# pcb_btt_tmc_2209.net
KiCad netlist of a schematic drawn in EAGLE
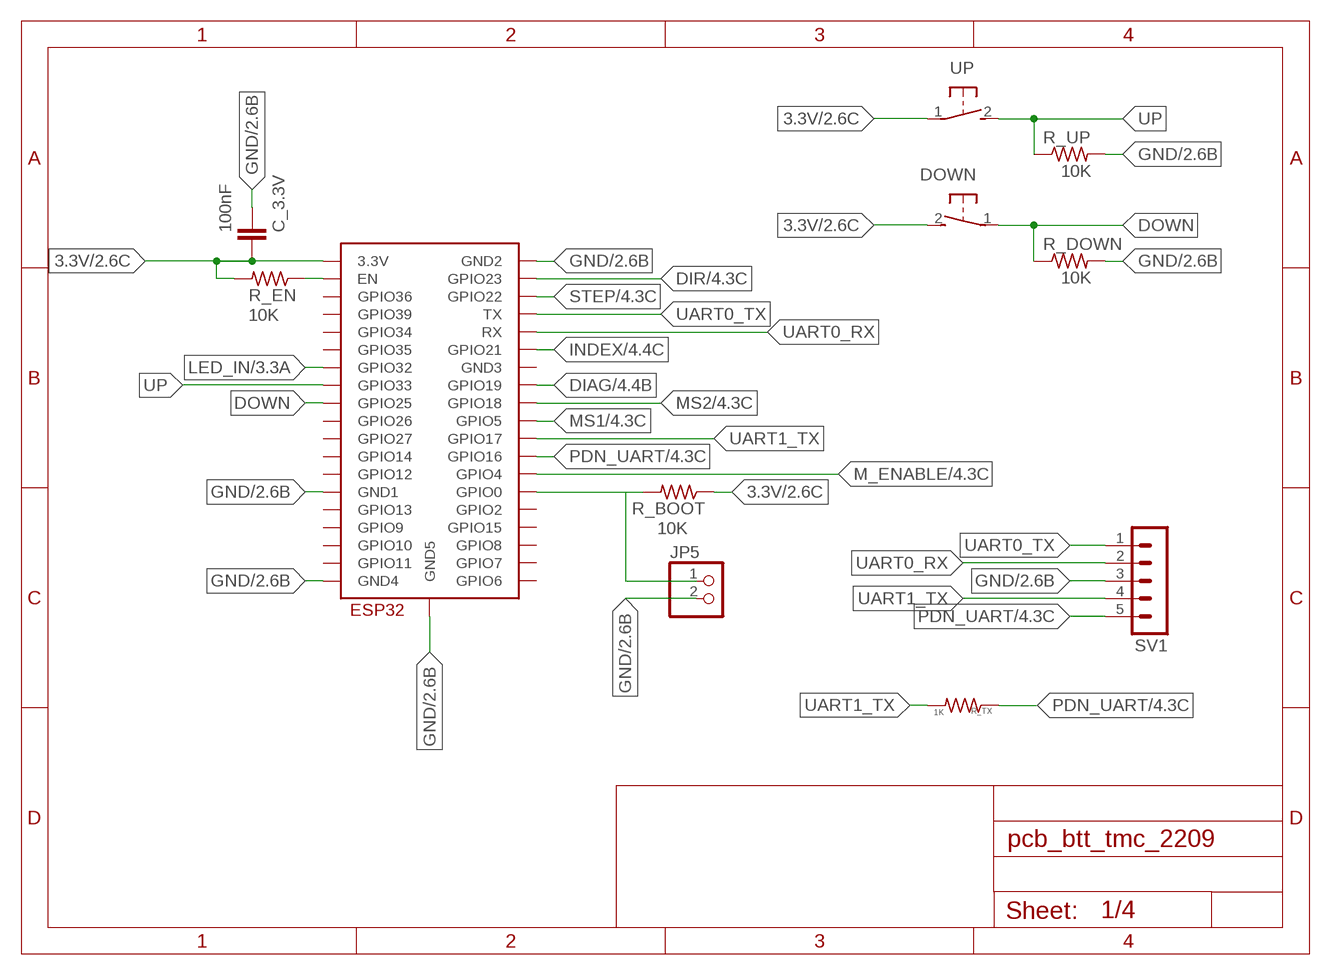
[diagram p0: schematic, sheet 1]
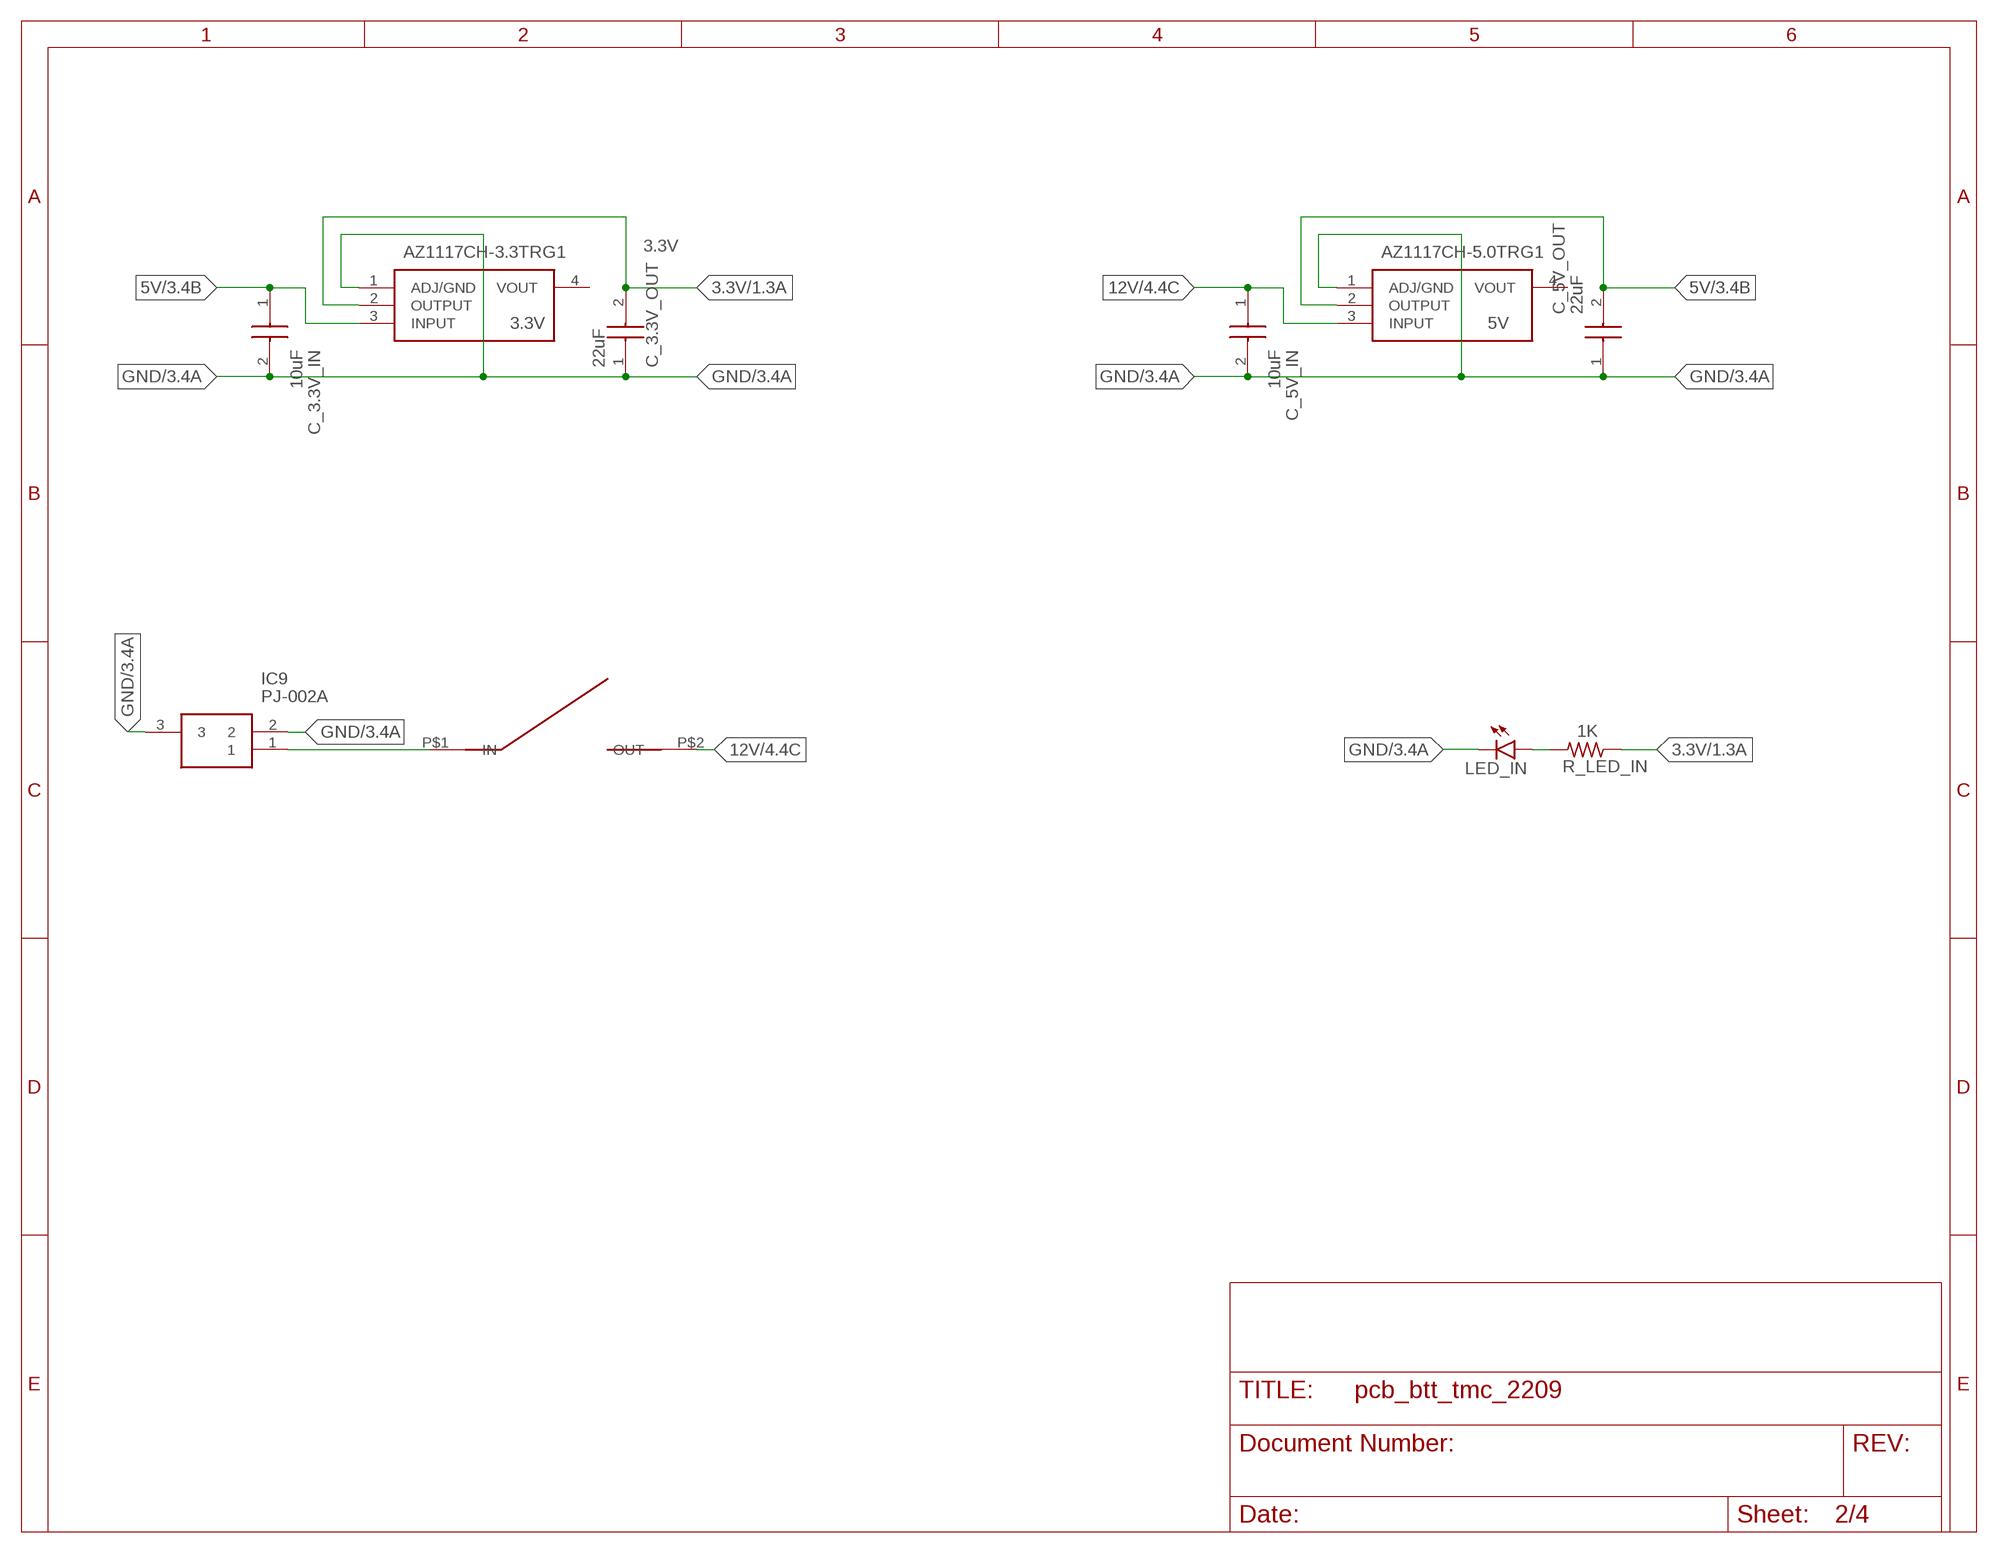
[diagram p1: schematic, sheet 2]
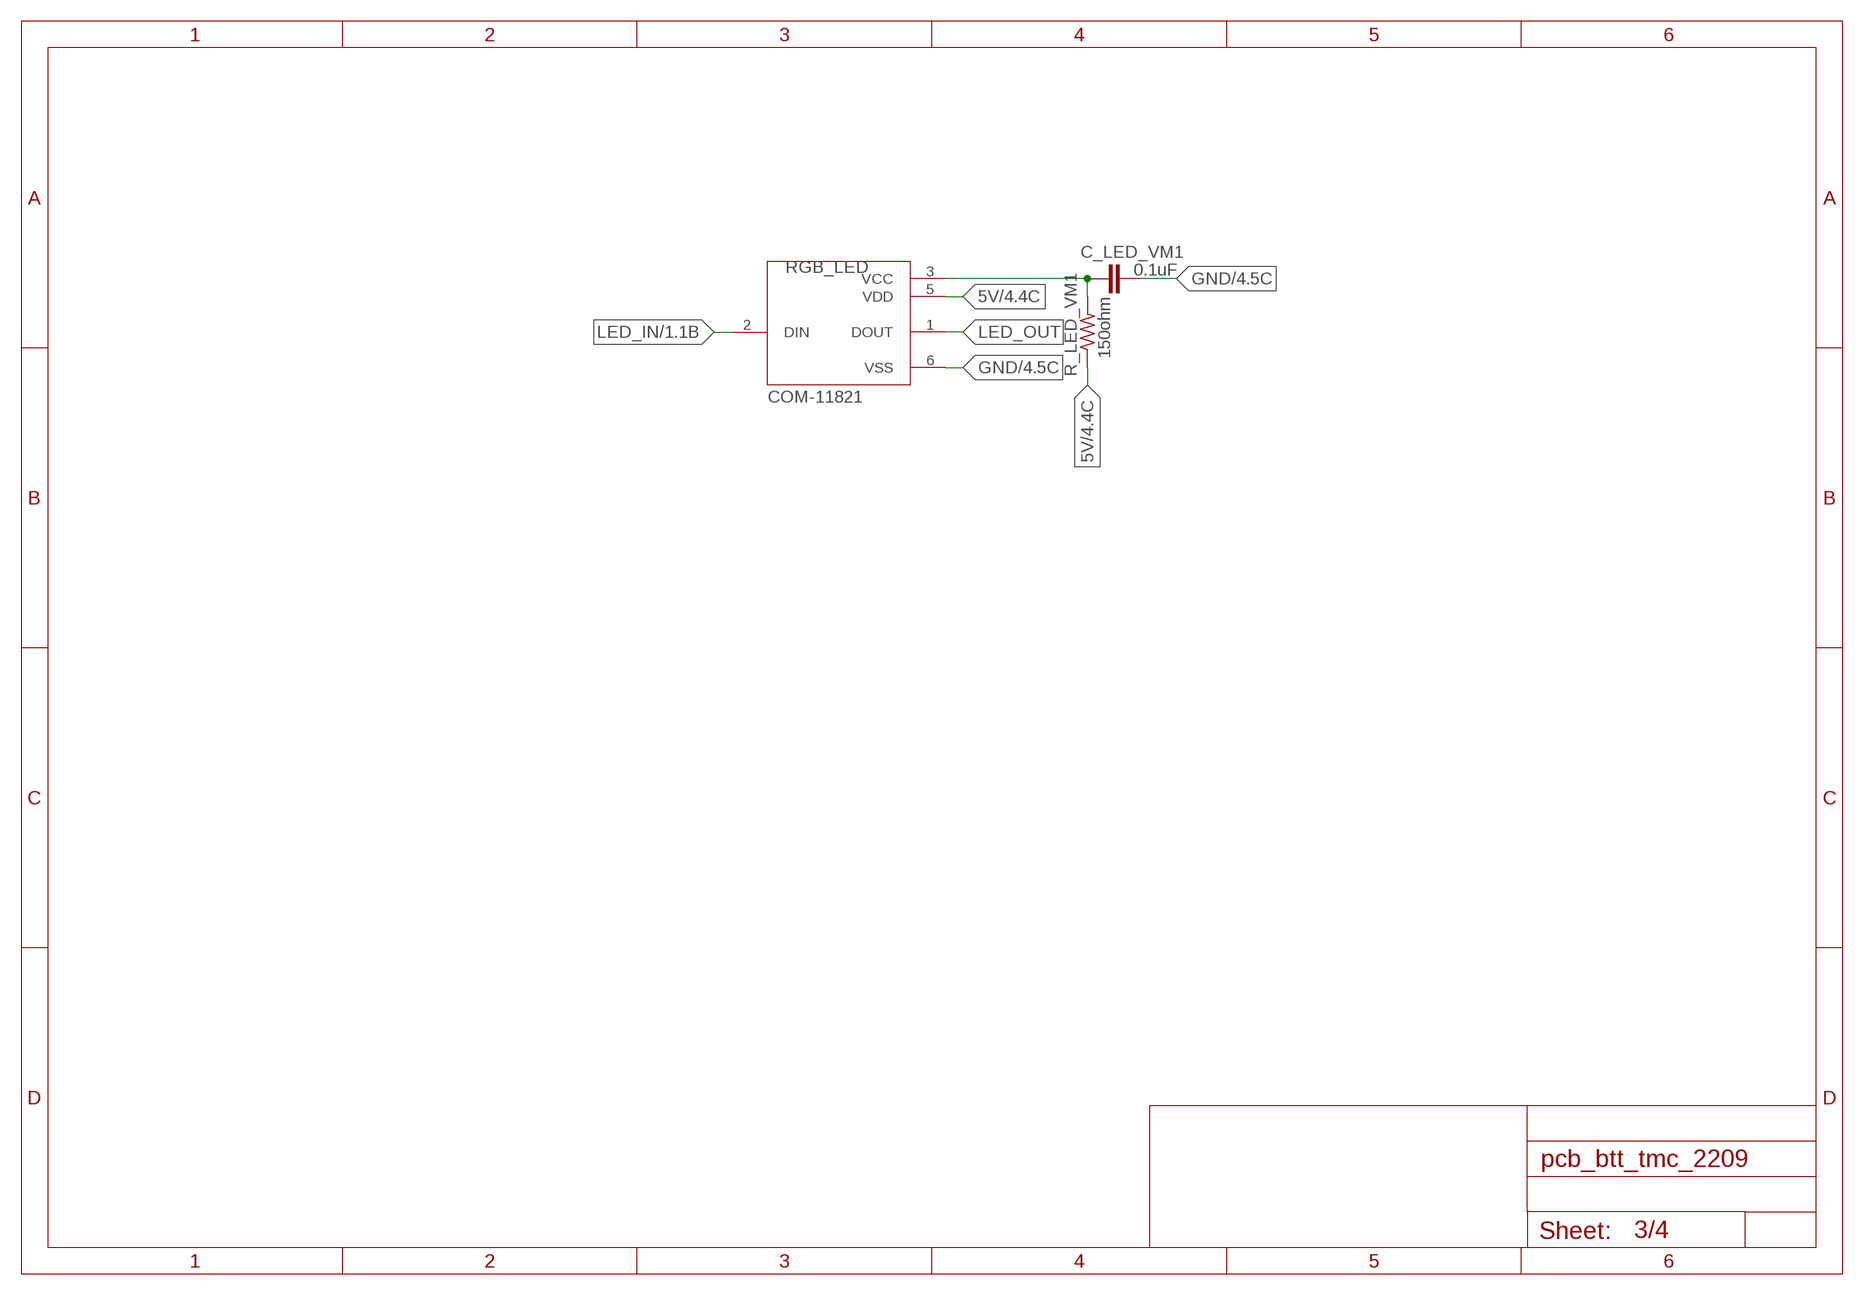
[diagram p2: schematic, sheet 3]
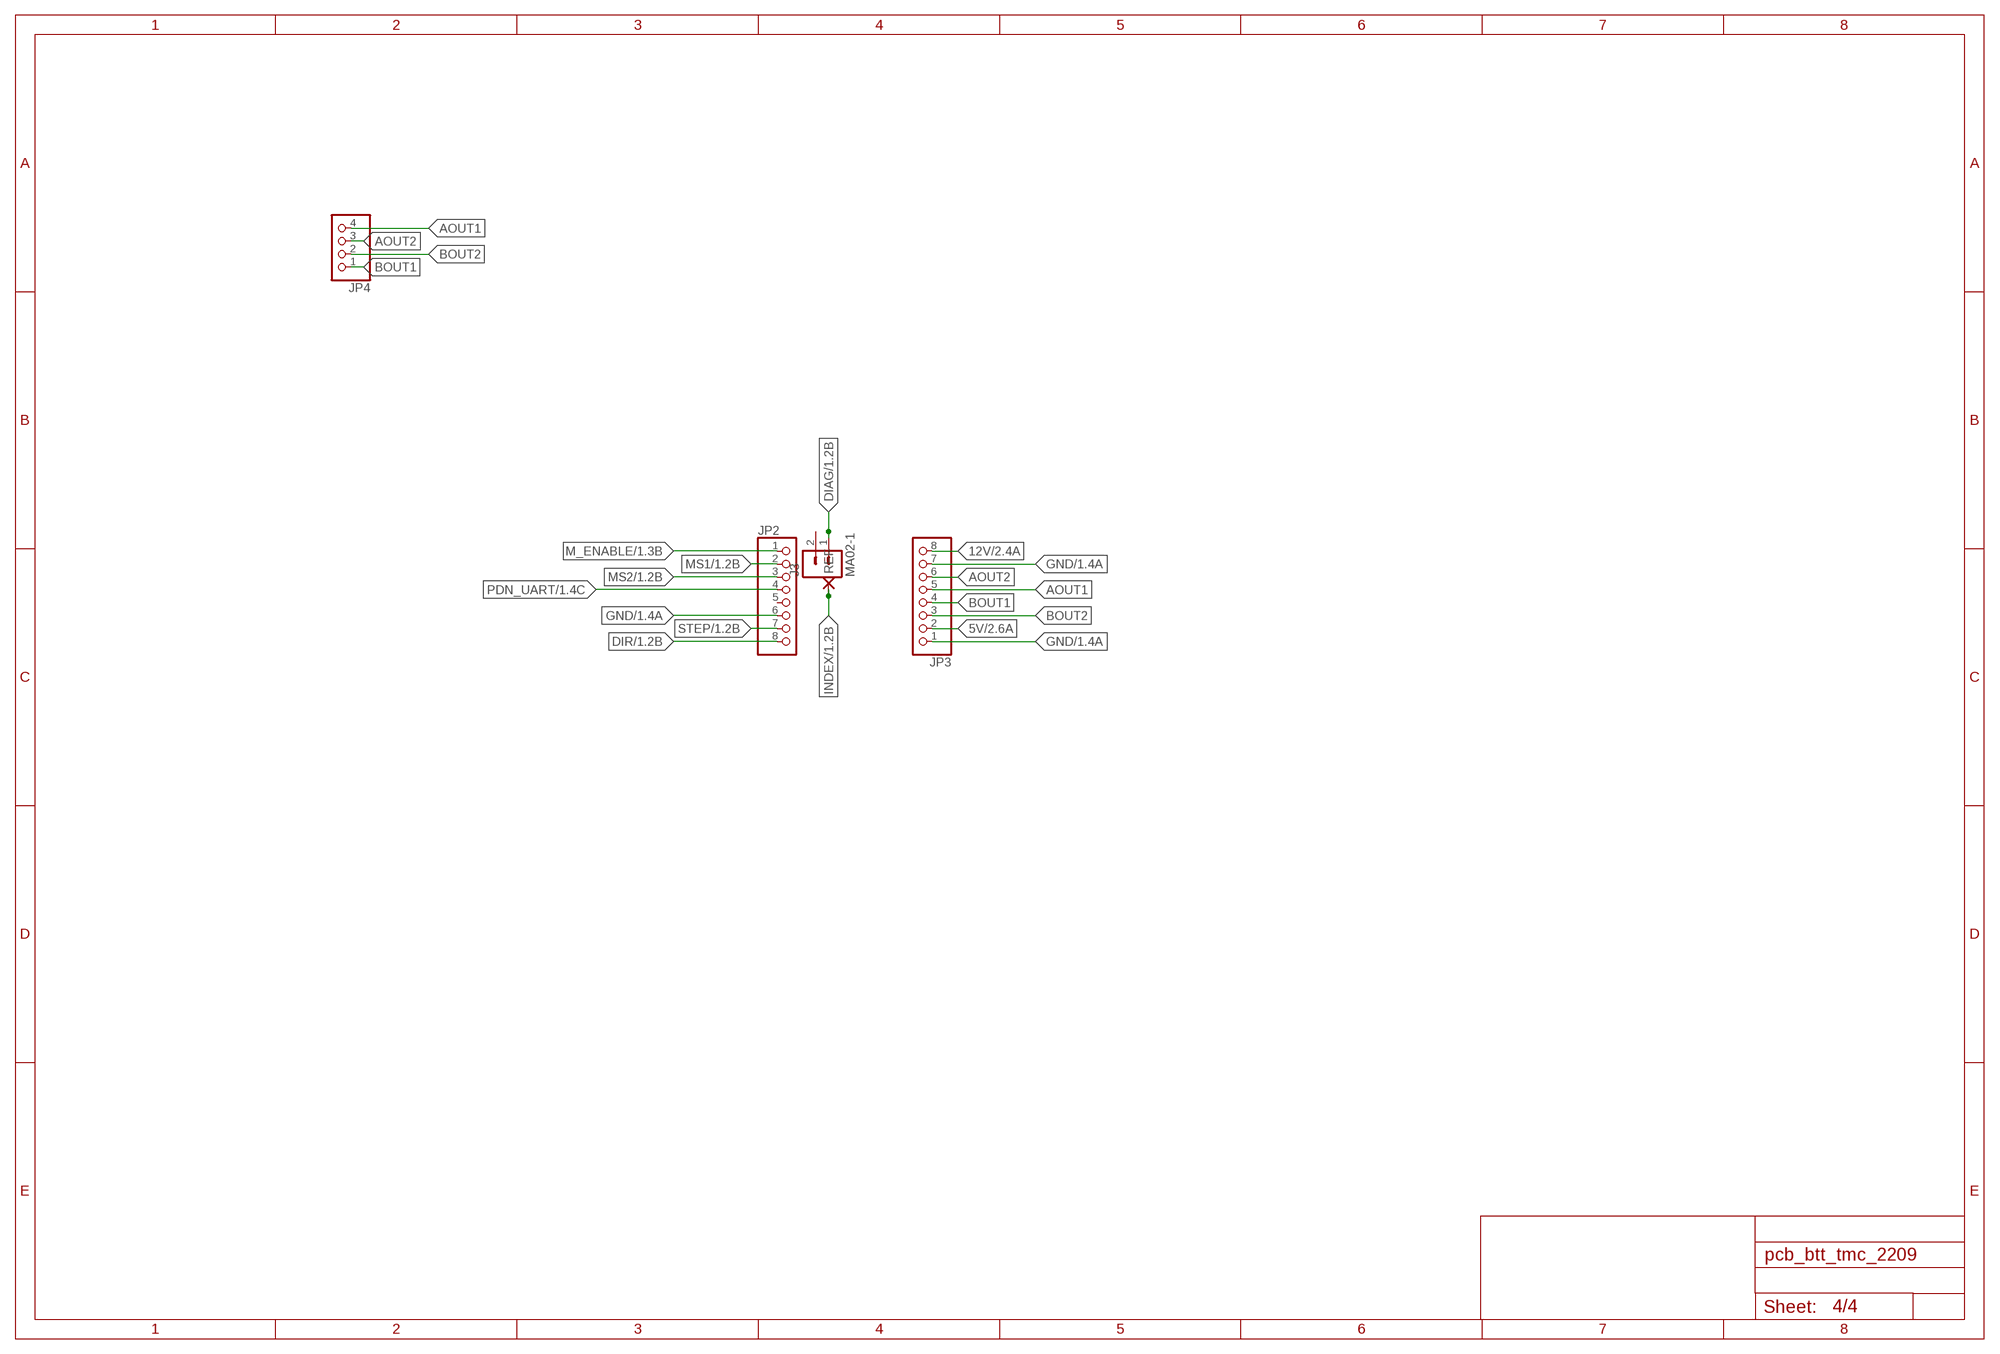
[diagram p3: schematic, sheet 4]

(export (version "E")
  (design (tool "Eeschema 10.0.6"))
  (components
    (comp (ref "C_LED_VM1")
      (value "0.1uF")
      (footprint "eagle-import:C0805K")
      (libsource (lib "eagle-import") (part "C-EUC0805K"))
    )
    (comp (ref "RGB_LED")
      (value "COM-11821")
      (footprint "eagle-import:LED_COM-11821")
      (fields (field (name "MF") "SparkFun Electronics"))
      (libsource (lib "eagle-import") (part "COM-11821"))
    )
    (comp (ref "R_LED_VM1")
      (value "150ohm")
      (footprint "eagle-import:R0805")
      (libsource (lib "eagle-import") (part "R-US_R0805"))
    )
    (comp (ref "3.3V")
      (value "AZ1117CH-3.3TRG1")
      (footprint "eagle-import:SOT230P700X180-4N")
      (fields (field (name "MOUSER_PART_NUMBER") "621-AZ1117CH-3.3TRG1"))
      (libsource (lib "eagle-import") (part "AZ1117CH-3.3TRG1"))
    )
    (comp (ref "5V")
      (value "AZ1117CH-5.0TRG1")
      (footprint "eagle-import:SOT230P700X180-4N")
      (fields (field (name "MOUSER_PART_NUMBER") "621-AZ1117CH-5.0TRG1"))
      (libsource (lib "eagle-import") (part "AZ1117CH-5.0TRG1"))
    )
    (comp (ref "C_3.3V_IN")
      (value "10uF")
      (footprint "eagle-import:CAPC2013X95N")
      (fields
        (field (name "MANUFACTURER_PART_NUMBER") "EMK212ABJ106KD-T")
        (field (name "MOUSER_PART_NUMBER") "963-EMK212ABJ106KD-T")
      )
      (libsource (lib "eagle-import") (part "EMK212ABJ106KD-T"))
    )
    (comp (ref "C_3.3V_OUT")
      (value "22uF")
      (footprint "eagle-import:CAPC3216X100N")
      (fields
        (field (name "MANUFACTURER_PART_NUMBER") "CL31A226MOCLNNC")
        (field (name "MOUSER_PART_NUMBER") "187-CL31A226MOCLNNC")
      )
      (libsource (lib "eagle-import") (part "CL31A226MOCLNNC"))
    )
    (comp (ref "C_5V_IN")
      (value "10uF")
      (footprint "eagle-import:CAPC2013X95N")
      (fields
        (field (name "MANUFACTURER_PART_NUMBER") "EMK212ABJ106KD-T")
        (field (name "MOUSER_PART_NUMBER") "963-EMK212ABJ106KD-T")
      )
      (libsource (lib "eagle-import") (part "EMK212ABJ106KD-T"))
    )
    (comp (ref "C_5V_OUT")
      (value "22uF")
      (footprint "eagle-import:CAPC3216X100N")
      (fields
        (field (name "MANUFACTURER_PART_NUMBER") "CL31A226MOCLNNC")
        (field (name "MOUSER_PART_NUMBER") "187-CL31A226MOCLNNC")
      )
      (libsource (lib "eagle-import") (part "CL31A226MOCLNNC"))
    )
    (comp (ref "IC9")
      (value "PJ-002A")
      (footprint "eagle-import:PJ002A")
      (fields (field (name "MOUSER_PART_NUMBER") "490-PJ-002A"))
      (libsource (lib "eagle-import") (part "PJ-002A"))
    )
    (comp (ref "LED_IN")
      (value "LEDSML0805")
      (footprint "eagle-import:SML0805")
      (libsource (lib "eagle-import") (part "LEDSML0805"))
    )
    (comp (ref "R_LED_IN")
      (value "1K")
      (footprint "eagle-import:R0805")
      (libsource (lib "eagle-import") (part "R-US_R0805"))
    )
    (comp (ref "U$1")
      (value "SPSTROCKERSWITCH2PIN")
      (footprint "eagle-import:SPST2PINROCKER")
      (libsource (lib "eagle-import") (part "SPSTROCKERSWITCH2PIN"))
    )
    (comp (ref "C_3.3V")
      (value "100nF")
      (footprint "eagle-import:C0805K")
      (libsource (lib "eagle-import") (part "C-EUC0805K"))
    )
    (comp (ref "DOWN")
      (value "31-XX")
      (footprint "eagle-import:B3F-31XX")
      (fields (field (name "MPN") "B3F-3100"))
      (libsource (lib "eagle-import") (part "31-XX"))
    )
    (comp (ref "JP5")
      (value "PINHD-1X2")
      (footprint "eagle-import:1X02")
      (libsource (lib "eagle-import") (part "PINHD-1X2"))
    )
    (comp (ref "R_BOOT")
      (value "10K")
      (footprint "eagle-import:R0805")
      (libsource (lib "eagle-import") (part "R-US_R0805"))
    )
    (comp (ref "R_DOWN")
      (value "10K")
      (footprint "eagle-import:R0805")
      (libsource (lib "eagle-import") (part "R-US_R0805"))
    )
    (comp (ref "R_EN")
      (value "10K")
      (footprint "eagle-import:R0805")
      (libsource (lib "eagle-import") (part "R-US_R0805"))
    )
    (comp (ref "R_TX")
      (value "1K")
      (footprint "eagle-import:R0805")
      (libsource (lib "eagle-import") (part "R-US_R0805"))
    )
    (comp (ref "R_UP")
      (value "10K")
      (footprint "eagle-import:R0805")
      (libsource (lib "eagle-import") (part "R-US_R0805"))
    )
    (comp (ref "SV1")
      (value "MA05-1")
      (footprint "eagle-import:MA05-1")
      (libsource (lib "eagle-import") (part "MA05-1"))
    )
    (comp (ref "U$2")
      (value "ESP32-WROOM")
      (footprint "eagle-import:ESP32-WROOM")
      (libsource (lib "eagle-import") (part "ESP32-WROOM"))
    )
    (comp (ref "UP")
      (value "31-XX")
      (footprint "eagle-import:B3F-31XX")
      (fields (field (name "MPN") "B3F-3100"))
      (libsource (lib "eagle-import") (part "31-XX"))
    )
    (comp (ref "J3")
      (value "MA02-1")
      (footprint "eagle-import:MA02-1")
      (libsource (lib "eagle-import") (part "MA02-1"))
    )
    (comp (ref "JP2")
      (value "PINHD-1X8")
      (footprint "eagle-import:1X08")
      (libsource (lib "eagle-import") (part "PINHD-1X8"))
    )
    (comp (ref "JP3")
      (value "PINHD-1X8")
      (footprint "eagle-import:1X08")
      (libsource (lib "eagle-import") (part "PINHD-1X8"))
    )
    (comp (ref "JP4")
      (value "PINHD-1X4")
      (footprint "eagle-import:1X04")
      (libsource (lib "eagle-import") (part "PINHD-1X4"))
    )
    (comp (ref "REF")
      (value "PAD-0.6-1.1")
      (footprint "eagle-import:PAD-0.6-1.1")
      (libsource (lib "eagle-import") (part "PAD-0.6-1.1"))
    )
  )
  (nets
    (net (code "1") (name "3.3V") (class "Default")
      (node (ref "3.3V") (pin "2") (pinfunction "OUTPUT_2") (pintype "bidirectional"))
      (node (ref "C_3.3V") (pin "2") (pinfunction "2_2") (pintype "passive"))
      (node (ref "C_3.3V_OUT") (pin "2") (pinfunction "2_2") (pintype "bidirectional"))
      (node (ref "DOWN") (pin "2") (pinfunction "S_2") (pintype "passive"))
      (node (ref "R_BOOT") (pin "1") (pinfunction "1_1") (pintype "passive"))
      (node (ref "R_EN") (pin "2") (pinfunction "2_2") (pintype "passive"))
      (node (ref "R_LED_IN") (pin "1") (pinfunction "1_1") (pintype "passive"))
      (node (ref "U$2") (pin "3V3") (pinfunction "3.3V_3V3") (pintype "bidirectional"))
      (node (ref "UP") (pin "1") (pinfunction "P_1") (pintype "passive"))
    )
    (net (code "2") (name "5V") (class "Default")
      (node (ref "3.3V") (pin "3") (pinfunction "INPUT_3") (pintype "bidirectional"))
      (node (ref "5V") (pin "2") (pinfunction "OUTPUT_2") (pintype "bidirectional"))
      (node (ref "C_3.3V_IN") (pin "1") (pinfunction "1_1") (pintype "bidirectional"))
      (node (ref "C_5V_OUT") (pin "2") (pinfunction "2_2") (pintype "bidirectional"))
      (node (ref "JP3") (pin "2") (pinfunction "2_2") (pintype "passive"))
      (node (ref "RGB_LED") (pin "5") (pinfunction "VDD_5") (pintype "power_in"))
      (node (ref "R_LED_VM1") (pin "1") (pinfunction "1_1") (pintype "passive"))
    )
    (net (code "3") (name "12V") (class "Default")
      (node (ref "5V") (pin "3") (pinfunction "INPUT_3") (pintype "bidirectional"))
      (node (ref "C_5V_IN") (pin "1") (pinfunction "1_1") (pintype "bidirectional"))
      (node (ref "JP3") (pin "8") (pinfunction "8_8") (pintype "passive"))
      (node (ref "U$1") (pin "P$2") (pinfunction "OUT_P$2") (pintype "bidirectional"))
    )
    (net (code "4") (name "AOUT1") (class "Default")
      (node (ref "JP3") (pin "5") (pinfunction "5_5") (pintype "passive"))
      (node (ref "JP4") (pin "4") (pinfunction "4_4") (pintype "passive"))
    )
    (net (code "5") (name "AOUT2") (class "Default")
      (node (ref "JP3") (pin "6") (pinfunction "6_6") (pintype "passive"))
      (node (ref "JP4") (pin "3") (pinfunction "3_3") (pintype "passive"))
    )
    (net (code "6") (name "BOUT1") (class "Default")
      (node (ref "JP3") (pin "4") (pinfunction "4_4") (pintype "passive"))
      (node (ref "JP4") (pin "1") (pinfunction "1_1") (pintype "passive"))
    )
    (net (code "7") (name "BOUT2") (class "Default")
      (node (ref "JP3") (pin "3") (pinfunction "3_3") (pintype "passive"))
      (node (ref "JP4") (pin "2") (pinfunction "2_2") (pintype "passive"))
    )
    (net (code "8") (name "DIAG") (class "Default")
      (node (ref "J3") (pin "1") (pinfunction "1_1") (pintype "passive"))
      (node (ref "U$2") (pin "IO19") (pinfunction "GPIO19_IO19") (pintype "bidirectional"))
    )
    (net (code "9") (name "DIR") (class "Default")
      (node (ref "JP2") (pin "8") (pinfunction "8_8") (pintype "passive"))
      (node (ref "U$2") (pin "IO23") (pinfunction "GPIO23_IO23") (pintype "bidirectional"))
    )
    (net (code "10") (name "DOWN") (class "Default")
      (node (ref "DOWN") (pin "1") (pinfunction "P_1") (pintype "passive"))
      (node (ref "R_DOWN") (pin "1") (pinfunction "1_1") (pintype "passive"))
      (node (ref "U$2") (pin "IO25") (pinfunction "GPIO25_IO25") (pintype "bidirectional"))
    )
    (net (code "11") (name "GND") (class "Default")
      (node (ref "3.3V") (pin "1") (pinfunction "ADJ/GND_1") (pintype "bidirectional"))
      (node (ref "5V") (pin "1") (pinfunction "ADJ/GND_1") (pintype "bidirectional"))
      (node (ref "C_3.3V") (pin "1") (pinfunction "1_1") (pintype "passive"))
      (node (ref "C_3.3V_IN") (pin "2") (pinfunction "2_2") (pintype "bidirectional"))
      (node (ref "C_3.3V_OUT") (pin "1") (pinfunction "1_1") (pintype "bidirectional"))
      (node (ref "C_5V_IN") (pin "2") (pinfunction "2_2") (pintype "bidirectional"))
      (node (ref "C_5V_OUT") (pin "1") (pinfunction "1_1") (pintype "bidirectional"))
      (node (ref "C_LED_VM1") (pin "2") (pinfunction "2_2") (pintype "passive"))
      (node (ref "IC9") (pin "2") (pinfunction "2_2") (pintype "bidirectional"))
      (node (ref "IC9") (pin "3") (pinfunction "3_3") (pintype "bidirectional"))
      (node (ref "JP2") (pin "6") (pinfunction "6_6") (pintype "passive"))
      (node (ref "JP3") (pin "1") (pinfunction "1_1") (pintype "passive"))
      (node (ref "JP3") (pin "7") (pinfunction "7_7") (pintype "passive"))
      (node (ref "JP5") (pin "2") (pinfunction "2_2") (pintype "passive"))
      (node (ref "LED_IN") (pin "C") (pinfunction "C_C") (pintype "passive"))
      (node (ref "RGB_LED") (pin "6") (pinfunction "VSS_6") (pintype "power_in"))
      (node (ref "R_DOWN") (pin "2") (pinfunction "2_2") (pintype "passive"))
      (node (ref "R_UP") (pin "2") (pinfunction "2_2") (pintype "passive"))
      (node (ref "SV1") (pin "3") (pinfunction "3_3") (pintype "passive"))
      (node (ref "U$2") (pin "GND1") (pinfunction "GND1_GND1") (pintype "bidirectional"))
      (node (ref "U$2") (pin "GND2") (pinfunction "GND2_GND2") (pintype "bidirectional"))
      (node (ref "U$2") (pin "GND4") (pinfunction "GND4_GND4") (pintype "bidirectional"))
      (node (ref "U$2") (pin "GND5") (pinfunction "GND5_GND5") (pintype "bidirectional"))
    )
    (net (code "12") (name "INDEX") (class "Default")
      (node (ref "REF") (pin "1") (pinfunction "P_1") (pintype "passive"))
      (node (ref "U$2") (pin "IO21") (pinfunction "GPIO21_IO21") (pintype "bidirectional"))
    )
    (net (code "13") (name "LED_IN") (class "Default")
      (node (ref "RGB_LED") (pin "2") (pinfunction "DIN_2") (pintype "input"))
      (node (ref "U$2") (pin "IO32") (pinfunction "GPIO32_IO32") (pintype "bidirectional"))
    )
    (net (code "14") (name "LED_OUT") (class "Default")
      (node (ref "RGB_LED") (pin "1") (pinfunction "DOUT_1") (pintype "output"))
    )
    (net (code "15") (name "MS1") (class "Default")
      (node (ref "JP2") (pin "2") (pinfunction "2_2") (pintype "passive"))
      (node (ref "U$2") (pin "IO5") (pinfunction "GPIO5_IO5") (pintype "bidirectional"))
    )
    (net (code "16") (name "MS2") (class "Default")
      (node (ref "JP2") (pin "3") (pinfunction "3_3") (pintype "passive"))
      (node (ref "U$2") (pin "IO18") (pinfunction "GPIO18_IO18") (pintype "bidirectional"))
    )
    (net (code "17") (name "M_ENABLE") (class "Default")
      (node (ref "JP2") (pin "1") (pinfunction "1_1") (pintype "passive"))
      (node (ref "U$2") (pin "IO4") (pinfunction "GPIO4_IO4") (pintype "bidirectional"))
    )
    (net (code "18") (name "Net-(LED_IN-PadA)") (class "Default")
      (node (ref "LED_IN") (pin "A") (pinfunction "A_A") (pintype "passive"))
      (node (ref "R_LED_IN") (pin "2") (pinfunction "2_2") (pintype "passive"))
    )
    (net (code "19") (name "Net-(RGB_LED-VCC)") (class "Default")
      (node (ref "C_LED_VM1") (pin "1") (pinfunction "1_1") (pintype "passive"))
      (node (ref "RGB_LED") (pin "3") (pinfunction "VCC_3") (pintype "power_in"))
      (node (ref "R_LED_VM1") (pin "2") (pinfunction "2_2") (pintype "passive"))
    )
    (net (code "20") (name "Net-(R_EN-Pad1)") (class "Default")
      (node (ref "R_EN") (pin "1") (pinfunction "1_1") (pintype "passive"))
      (node (ref "U$2") (pin "EN") (pinfunction "EN_EN") (pintype "bidirectional"))
    )
    (net (code "21") (name "Net-(U$1-IN)") (class "Default")
      (node (ref "IC9") (pin "1") (pinfunction "1_1") (pintype "bidirectional"))
      (node (ref "U$1") (pin "P$1") (pinfunction "IN_P$1") (pintype "bidirectional"))
    )
    (net (code "22") (name "Net-(U$2-GPIO0)") (class "Default")
      (node (ref "JP5") (pin "1") (pinfunction "1_1") (pintype "passive"))
      (node (ref "R_BOOT") (pin "2") (pinfunction "2_2") (pintype "passive"))
      (node (ref "U$2") (pin "IO0") (pinfunction "GPIO0_IO0") (pintype "bidirectional"))
    )
    (net (code "23") (name "PDN_UART") (class "Default")
      (node (ref "JP2") (pin "4") (pinfunction "4_4") (pintype "passive"))
      (node (ref "R_TX") (pin "1") (pinfunction "1_1") (pintype "passive"))
      (node (ref "SV1") (pin "5") (pinfunction "5_5") (pintype "passive"))
      (node (ref "U$2") (pin "IO16") (pinfunction "GPIO16_IO16") (pintype "bidirectional"))
    )
    (net (code "24") (name "STEP") (class "Default")
      (node (ref "JP2") (pin "7") (pinfunction "7_7") (pintype "passive"))
      (node (ref "U$2") (pin "IO22") (pinfunction "GPIO22_IO22") (pintype "bidirectional"))
    )
    (net (code "25") (name "UART0_RX") (class "Default")
      (node (ref "SV1") (pin "2") (pinfunction "2_2") (pintype "passive"))
      (node (ref "U$2") (pin "RX") (pinfunction "RX_RX") (pintype "bidirectional"))
    )
    (net (code "26") (name "UART0_TX") (class "Default")
      (node (ref "SV1") (pin "1") (pinfunction "1_1") (pintype "passive"))
      (node (ref "U$2") (pin "TX") (pinfunction "TX_TX") (pintype "bidirectional"))
    )
    (net (code "27") (name "UART1_TX") (class "Default")
      (node (ref "R_TX") (pin "2") (pinfunction "2_2") (pintype "passive"))
      (node (ref "SV1") (pin "4") (pinfunction "4_4") (pintype "passive"))
      (node (ref "U$2") (pin "IO17") (pinfunction "GPIO17_IO17") (pintype "bidirectional"))
    )
    (net (code "28") (name "UP") (class "Default")
      (node (ref "R_UP") (pin "1") (pinfunction "1_1") (pintype "passive"))
      (node (ref "U$2") (pin "IO33") (pinfunction "GPIO33_IO33") (pintype "bidirectional"))
      (node (ref "UP") (pin "2") (pinfunction "S_2") (pintype "passive"))
    )
    (net (code "29") (name "unconnected-(3.3V-VOUT-Pad4)") (class "Default")
      (node (ref "3.3V") (pin "4") (pinfunction "VOUT_4") (pintype "bidirectional"))
    )
    (net (code "30") (name "unconnected-(5V-VOUT-Pad4)") (class "Default")
      (node (ref "5V") (pin "4") (pinfunction "VOUT_4") (pintype "bidirectional"))
    )
    (net (code "31") (name "unconnected-(J3-Pad2)") (class "Default")
      (node (ref "J3") (pin "2") (pinfunction "2_2") (pintype "passive"))
    )
    (net (code "32") (name "unconnected-(JP2-Pad5)") (class "Default")
      (node (ref "JP2") (pin "5") (pinfunction "5_5") (pintype "passive"))
    )
    (net (code "33") (name "unconnected-(U$2-GPIO2-PadIO2)") (class "Default")
      (node (ref "U$2") (pin "IO2") (pinfunction "GPIO2_IO2") (pintype "bidirectional"))
    )
    (net (code "34") (name "unconnected-(U$2-GPIO6-PadCLK)") (class "Default")
      (node (ref "U$2") (pin "CLK") (pinfunction "GPIO6_CLK") (pintype "bidirectional"))
    )
    (net (code "35") (name "unconnected-(U$2-GPIO7-PadSD0)") (class "Default")
      (node (ref "U$2") (pin "SD0") (pinfunction "GPIO7_SD0") (pintype "bidirectional"))
    )
    (net (code "36") (name "unconnected-(U$2-GPIO8-PadSD1)") (class "Default")
      (node (ref "U$2") (pin "SD1") (pinfunction "GPIO8_SD1") (pintype "bidirectional"))
    )
    (net (code "37") (name "unconnected-(U$2-GPIO9-PadSD2)") (class "Default")
      (node (ref "U$2") (pin "SD2") (pinfunction "GPIO9_SD2") (pintype "bidirectional"))
    )
    (net (code "38") (name "unconnected-(U$2-GPIO10-PadSD3)") (class "Default")
      (node (ref "U$2") (pin "SD3") (pinfunction "GPIO10_SD3") (pintype "bidirectional"))
    )
    (net (code "39") (name "unconnected-(U$2-GPIO11-PadCMD)") (class "Default")
      (node (ref "U$2") (pin "CMD") (pinfunction "GPIO11_CMD") (pintype "bidirectional"))
    )
    (net (code "40") (name "unconnected-(U$2-GPIO12-PadIO12)") (class "Default")
      (node (ref "U$2") (pin "IO12") (pinfunction "GPIO12_IO12") (pintype "bidirectional"))
    )
    (net (code "41") (name "unconnected-(U$2-GPIO13-PadIO13)") (class "Default")
      (node (ref "U$2") (pin "IO13") (pinfunction "GPIO13_IO13") (pintype "bidirectional"))
    )
    (net (code "42") (name "unconnected-(U$2-GPIO14-PadIO14)") (class "Default")
      (node (ref "U$2") (pin "IO14") (pinfunction "GPIO14_IO14") (pintype "bidirectional"))
    )
    (net (code "43") (name "unconnected-(U$2-GPIO15-PadIO15)") (class "Default")
      (node (ref "U$2") (pin "IO15") (pinfunction "GPIO15_IO15") (pintype "bidirectional"))
    )
    (net (code "44") (name "unconnected-(U$2-GPIO26-PadIO26)") (class "Default")
      (node (ref "U$2") (pin "IO26") (pinfunction "GPIO26_IO26") (pintype "bidirectional"))
    )
    (net (code "45") (name "unconnected-(U$2-GPIO27-PadIO27)") (class "Default")
      (node (ref "U$2") (pin "IO27") (pinfunction "GPIO27_IO27") (pintype "bidirectional"))
    )
    (net (code "46") (name "unconnected-(U$2-GPIO34-PadIO34)") (class "Default")
      (node (ref "U$2") (pin "IO34") (pinfunction "GPIO34_IO34") (pintype "bidirectional"))
    )
    (net (code "47") (name "unconnected-(U$2-GPIO35-PadIO35)") (class "Default")
      (node (ref "U$2") (pin "IO35") (pinfunction "GPIO35_IO35") (pintype "bidirectional"))
    )
    (net (code "48") (name "unconnected-(U$2-GPIO36-PadSENSOR_VP)") (class "Default")
      (node (ref "U$2") (pin "SENSOR_VP") (pinfunction "GPIO36_SENSOR_VP") (pintype "bidirectional"))
    )
    (net (code "49") (name "unconnected-(U$2-GPIO39-PadSENSOR_VN)") (class "Default")
      (node (ref "U$2") (pin "SENSOR_VN") (pinfunction "GPIO39_SENSOR_VN") (pintype "bidirectional"))
    )
    (net (code "50") (name "unconnected-(U$2-PadGND3)") (class "Default")
      (node (ref "U$2") (pin "GND3") (pinfunction "GND3_GND3") (pintype "bidirectional"))
    )
  )
)
